# RJ45_Connector.net
KiCad netlist of a schematic drawn in Altium Designer
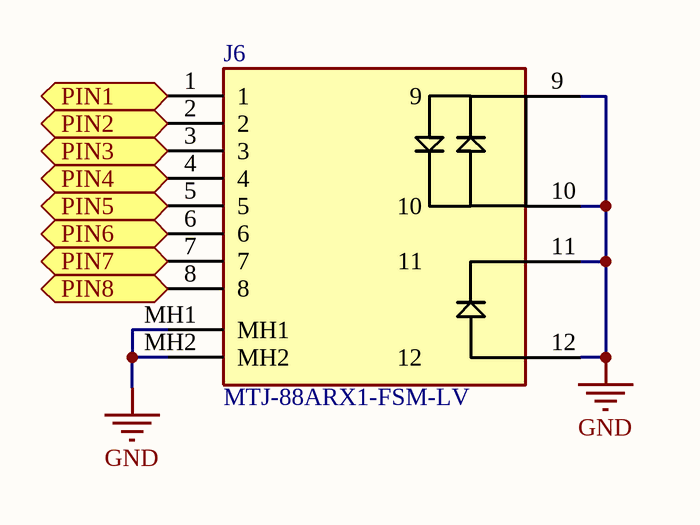
[diagram p0: RJ45 Connector.SchDoc]

(export (version "E")
  (design (tool "Eeschema 10.0.6"))
  (components
    (comp (ref "J6")
      (value "MTJ-88ARX1-FSM-LV")
      (footprint "MTJ-88ARX1-FSM-LV")
      (description "RJ45 Connector")
      (libsource (lib "GeneralConnectors") (part "MTJ-88ARX1-FSM-LV"))
    )
  )
  (nets
    (net (code "1") (name "/PIN1") (class "Default")
      (node (ref "J6") (pin "1") (pinfunction "1_1") (pintype "passive"))
    )
    (net (code "2") (name "/PIN2") (class "Default")
      (node (ref "J6") (pin "2") (pinfunction "2_2") (pintype "passive"))
    )
    (net (code "3") (name "/PIN3") (class "Default")
      (node (ref "J6") (pin "3") (pinfunction "3_3") (pintype "passive"))
    )
    (net (code "4") (name "/PIN4") (class "Default")
      (node (ref "J6") (pin "4") (pinfunction "4_4") (pintype "passive"))
    )
    (net (code "5") (name "/PIN5") (class "Default")
      (node (ref "J6") (pin "5") (pinfunction "5_5") (pintype "passive"))
    )
    (net (code "6") (name "/PIN6") (class "Default")
      (node (ref "J6") (pin "6") (pinfunction "6_6") (pintype "passive"))
    )
    (net (code "7") (name "/PIN7") (class "Default")
      (node (ref "J6") (pin "7") (pinfunction "7_7") (pintype "passive"))
    )
    (net (code "8") (name "/PIN8") (class "Default")
      (node (ref "J6") (pin "8") (pinfunction "8_8") (pintype "passive"))
    )
    (net (code "9") (name "GND") (class "Default")
      (node (ref "J6") (pin "10") (pinfunction "10_10") (pintype "passive"))
      (node (ref "J6") (pin "11") (pinfunction "11_11") (pintype "passive"))
      (node (ref "J6") (pin "12") (pinfunction "12_12") (pintype "passive"))
      (node (ref "J6") (pin "9") (pinfunction "9_9") (pintype "passive"))
      (node (ref "J6") (pin "MH1") (pinfunction "MH1_MH1") (pintype "passive"))
      (node (ref "J6") (pin "MH2") (pinfunction "MH2_MH2") (pintype "passive"))
    )
  )
)
